# KX1_DB_DAC_2.net
KiCad netlist of a schematic drawn in Altium Designer
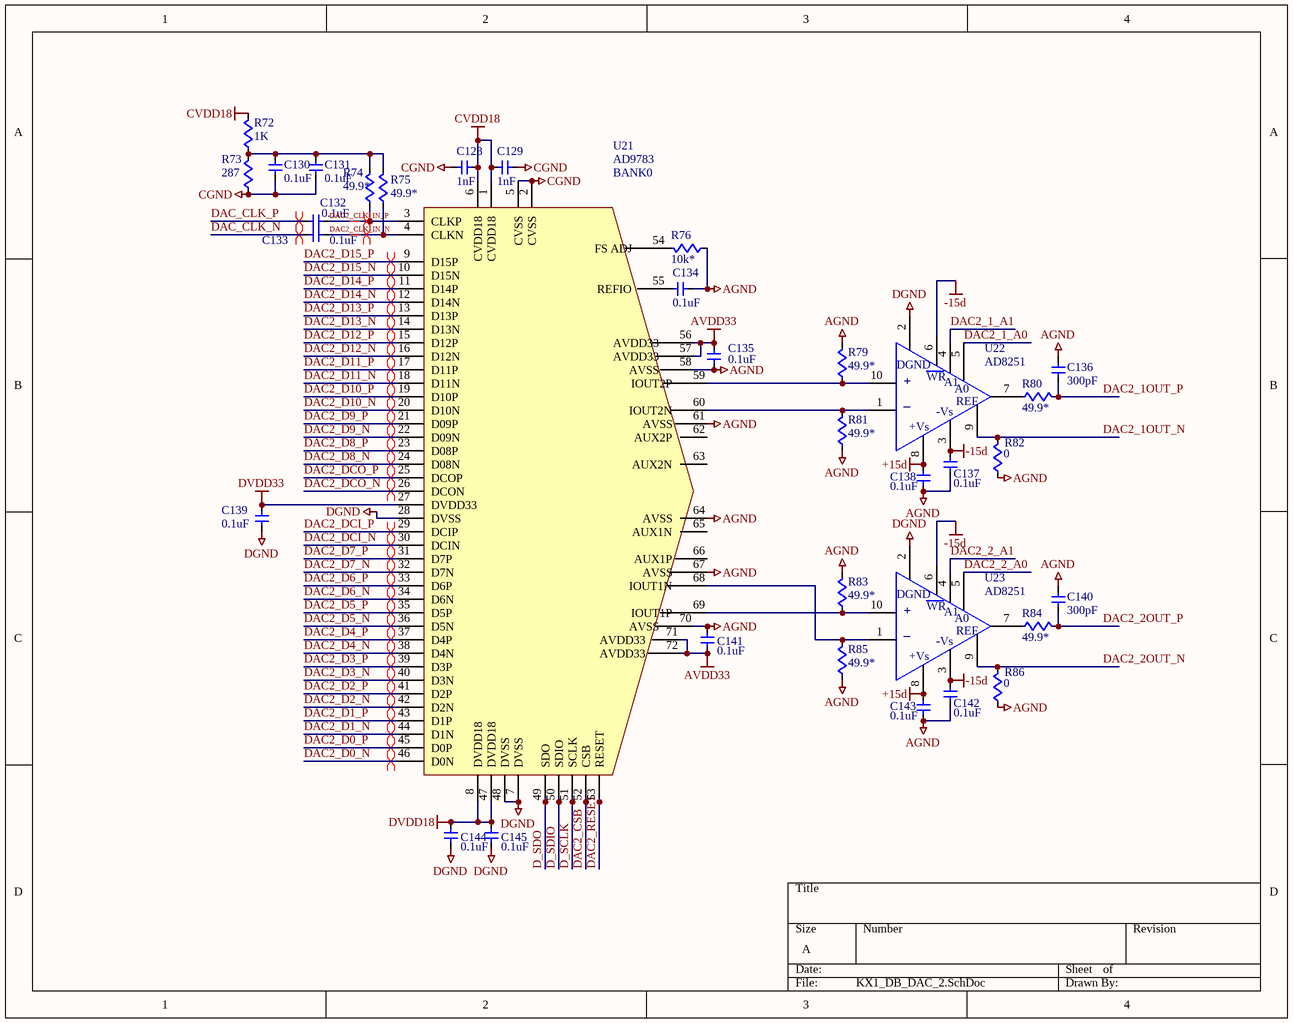
[diagram p0: KX1_DB_DAC_2.SchDoc]

(export (version "E")
  (design (tool "Eeschema 10.0.6"))
  (components
    (comp (ref "C128")
      (value "1nF")
      (footprint "0603w")
      (description "capacitor")
      (fields
        (field (name "MANUFACTURER") "Murata Electronics North America")
        (field (name "MANUFACTURER PART NUMBER") "GRM188R71H102KA01D")
      )
      (libsource (lib "KX1_DB") (part "CAP_SM_1"))
    )
    (comp (ref "C129")
      (value "1nF")
      (footprint "0603w")
      (description "capacitor")
      (fields
        (field (name "MANUFACTURER") "Murata Electronics North America")
        (field (name "MANUFACTURER PART NUMBER") "GRM188R71H102KA01D")
      )
      (libsource (lib "KX1_DB") (part "CAP_SM_1"))
    )
    (comp (ref "C130")
      (value "0.1uF")
      (footprint "0603w")
      (description "capacitor")
      (fields
        (field (name "MANUFACTURER") "Kemet")
        (field (name "MANUFACTURER PART NUMBER") "C0603C104K3RACTU")
      )
      (libsource (lib "KX1_DB") (part "CAP_SM"))
    )
    (comp (ref "C131")
      (value "0.1uF")
      (footprint "0603w")
      (description "capacitor")
      (fields
        (field (name "MANUFACTURER") "Kemet")
        (field (name "MANUFACTURER PART NUMBER") "C0603C104K3RACTU")
      )
      (libsource (lib "KX1_DB") (part "CAP_SM"))
    )
    (comp (ref "C132")
      (value "0.1uF")
      (footprint "1206")
      (description "capacitor")
      (fields
        (field (name "MANUFACTURER") "Murata Electronics North America")
        (field (name "MANUFACTURER PART NUMBER") "GRM31C5C1E104JA01L")
      )
      (libsource (lib "KX1_DB") (part "CAP_SM_1"))
    )
    (comp (ref "C133")
      (value "0.1uF")
      (footprint "1206")
      (description "capacitor")
      (fields
        (field (name "MANUFACTURER") "Murata Electronics North America")
        (field (name "MANUFACTURER PART NUMBER") "GRM31C5C1E104JA01L")
      )
      (libsource (lib "KX1_DB") (part "CAP_SM_1"))
    )
    (comp (ref "C134")
      (value "0.1uF")
      (footprint "0603w")
      (description "capacitor")
      (fields
        (field (name "MANUFACTURER") "Kemet")
        (field (name "MANUFACTURER PART NUMBER") "C0603C104K3RACTU")
      )
      (libsource (lib "KX1_DB") (part "CAP_SM_1"))
    )
    (comp (ref "C135")
      (value "0.1uF")
      (footprint "0603w")
      (description "capacitor")
      (fields
        (field (name "MANUFACTURER") "Kemet")
        (field (name "MANUFACTURER PART NUMBER") "C0603C104K3RACTU")
      )
      (libsource (lib "KX1_DB") (part "CAP_SM_1"))
    )
    (comp (ref "C136")
      (value "300pF")
      (footprint "0603w")
      (description "capacitor")
      (libsource (lib "KX1_DB") (part "CAP_SM_1"))
    )
    (comp (ref "C137")
      (value "0.1uF")
      (footprint "0603w")
      (description "capacitor")
      (fields
        (field (name "MANUFACTURER") "Kemet")
        (field (name "MANUFACTURER PART NUMBER") "C0603C104K3RACTU")
      )
      (libsource (lib "KX1_DB") (part "CAP_SM_1"))
    )
    (comp (ref "C138")
      (value "0.1uF")
      (footprint "0603w")
      (description "capacitor")
      (fields
        (field (name "MANUFACTURER") "Kemet")
        (field (name "MANUFACTURER PART NUMBER") "C0603C104K3RACTU")
      )
      (libsource (lib "KX1_DB") (part "CAP_SM_1"))
    )
    (comp (ref "C139")
      (value "0.1uF")
      (footprint "0603w")
      (description "capacitor")
      (fields
        (field (name "MANUFACTURER") "Kemet")
        (field (name "MANUFACTURER PART NUMBER") "C0603C104K3RACTU")
      )
      (libsource (lib "KX1_DB") (part "CAP_SM_1"))
    )
    (comp (ref "C140")
      (value "300pF")
      (footprint "0603w")
      (description "capacitor")
      (libsource (lib "KX1_DB") (part "CAP_SM_1"))
    )
    (comp (ref "C141")
      (value "0.1uF")
      (footprint "0603w")
      (description "capacitor")
      (fields
        (field (name "MANUFACTURER") "Kemet")
        (field (name "MANUFACTURER PART NUMBER") "C0603C104K3RACTU")
      )
      (libsource (lib "KX1_DB") (part "CAP_SM_1"))
    )
    (comp (ref "C142")
      (value "0.1uF")
      (footprint "0603w")
      (description "capacitor")
      (fields
        (field (name "MANUFACTURER") "Kemet")
        (field (name "MANUFACTURER PART NUMBER") "C0603C104K3RACTU")
      )
      (libsource (lib "KX1_DB") (part "CAP_SM_1"))
    )
    (comp (ref "C143")
      (value "0.1uF")
      (footprint "0603w")
      (description "capacitor")
      (fields
        (field (name "MANUFACTURER") "Kemet")
        (field (name "MANUFACTURER PART NUMBER") "C0603C104K3RACTU")
      )
      (libsource (lib "KX1_DB") (part "CAP_SM_1"))
    )
    (comp (ref "C144")
      (value "0.1uF")
      (footprint "0603w")
      (description "capacitor")
      (fields
        (field (name "MANUFACTURER") "Kemet")
        (field (name "MANUFACTURER PART NUMBER") "C0603C104K3RACTU")
      )
      (libsource (lib "KX1_DB") (part "CAP_SM_1"))
    )
    (comp (ref "C145")
      (value "0.1uF")
      (footprint "0603w")
      (description "capacitor")
      (fields
        (field (name "MANUFACTURER") "Kemet")
        (field (name "MANUFACTURER PART NUMBER") "C0603C104K3RACTU")
      )
      (libsource (lib "KX1_DB") (part "CAP_SM_1"))
    )
    (comp (ref "R72")
      (value "1K")
      (footprint "0603w")
      (description "resistor")
      (fields
        (field (name "MANUFACTURER") "Yageo")
        (field (name "MANUFACTURER PART NUMBER") "RC0603FR-071KL")
      )
      (libsource (lib "KX1_DB") (part "RES_SM"))
    )
    (comp (ref "R73")
      (value "287")
      (footprint "0603w")
      (description "resistor")
      (fields
        (field (name "MANUFACTURER") "Yageo")
        (field (name "MANUFACTURER PART NUMBER") "RC0603FR-07287RL")
      )
      (libsource (lib "KX1_DB") (part "RES_SM"))
    )
    (comp (ref "R74")
      (value "49.9*")
      (footprint "0603w")
      (description "resistor")
      (fields
        (field (name "MANUFACTURER") "Stackpole Electronics Inc")
        (field (name "MANUFACTURER PART NUMBER") "RNCS0603BKE49R9")
      )
      (libsource (lib "KX1_DB") (part "RES_SM"))
    )
    (comp (ref "R75")
      (value "49.9*")
      (footprint "0603w")
      (description "resistor")
      (fields
        (field (name "MANUFACTURER") "Stackpole Electronics Inc")
        (field (name "MANUFACTURER PART NUMBER") "RNCS0603BKE49R9")
      )
      (libsource (lib "KX1_DB") (part "RES_SM"))
    )
    (comp (ref "R76")
      (value "10k*")
      (footprint "0603w")
      (description "resistor")
      (fields
        (field (name "MANUFACTURER") "Susumu")
        (field (name "MANUFACTURER PART NUMBER") "RG1608P-103-B-T5")
      )
      (libsource (lib "KX1_DB") (part "RES_SM"))
    )
    (comp (ref "R79")
      (value "49.9*")
      (footprint "0603w")
      (description "resistor")
      (fields
        (field (name "MANUFACTURER") "Stackpole Electronics Inc")
        (field (name "MANUFACTURER PART NUMBER") "RNCS0603BKE49R9")
      )
      (libsource (lib "KX1_DB") (part "RES_SM"))
    )
    (comp (ref "R80")
      (value "49.9*")
      (footprint "0603w")
      (description "resistor")
      (fields
        (field (name "MANUFACTURER") "Stackpole Electronics Inc")
        (field (name "MANUFACTURER PART NUMBER") "RNCS0603BKE49R9")
      )
      (libsource (lib "KX1_DB") (part "RES_SM"))
    )
    (comp (ref "R81")
      (value "49.9*")
      (footprint "0603w")
      (description "resistor")
      (fields
        (field (name "MANUFACTURER") "Stackpole Electronics Inc")
        (field (name "MANUFACTURER PART NUMBER") "RNCS0603BKE49R9")
      )
      (libsource (lib "KX1_DB") (part "RES_SM"))
    )
    (comp (ref "R82")
      (value "0")
      (footprint "0603w")
      (description "resistor")
      (libsource (lib "KX1_DB") (part "RES_SM"))
    )
    (comp (ref "R83")
      (value "49.9*")
      (footprint "0603w")
      (description "resistor")
      (fields
        (field (name "MANUFACTURER") "Stackpole Electronics Inc")
        (field (name "MANUFACTURER PART NUMBER") "RNCS0603BKE49R9")
      )
      (libsource (lib "KX1_DB") (part "RES_SM"))
    )
    (comp (ref "R84")
      (value "49.9*")
      (footprint "0603w")
      (description "resistor")
      (fields
        (field (name "MANUFACTURER") "Stackpole Electronics Inc")
        (field (name "MANUFACTURER PART NUMBER") "RNCS0603BKE49R9")
      )
      (libsource (lib "KX1_DB") (part "RES_SM"))
    )
    (comp (ref "R85")
      (value "49.9*")
      (footprint "0603w")
      (description "resistor")
      (fields
        (field (name "MANUFACTURER") "Stackpole Electronics Inc")
        (field (name "MANUFACTURER PART NUMBER") "RNCS0603BKE49R9")
      )
      (libsource (lib "KX1_DB") (part "RES_SM"))
    )
    (comp (ref "R86")
      (value "0")
      (footprint "0603w")
      (description "resistor")
      (libsource (lib "KX1_DB") (part "RES_SM"))
    )
    (comp (ref "U21")
      (value "AD9783")
      (footprint "LFCSP72")
      (description "DAC LVDS DUAL16BIT 500MSPS")
      (libsource (lib "KX1_DB") (part "AD9783"))
    )
    (comp (ref "U22")
      (value "AD8251")
      (footprint "MSOP10sm")
      (description "IC AMP INST ICMOS LDRIFT 10MSOP")
      (libsource (lib "KX1_DB") (part "AD8251"))
    )
    (comp (ref "U23")
      (value "AD8251")
      (footprint "MSOP10sm")
      (description "IC AMP INST ICMOS LDRIFT 10MSOP")
      (libsource (lib "KX1_DB") (part "AD8251"))
    )
  )
  (nets
    (net (code "1") (name "+15d") (class "Default")
      (node (ref "C138") (pin "2") (pintype "passive"))
      (node (ref "C143") (pin "2") (pintype "passive"))
      (node (ref "U22") (pin "8") (pintype "passive"))
      (node (ref "U23") (pin "8") (pintype "passive"))
    )
    (net (code "2") (name "-15d") (class "Default")
      (node (ref "C137") (pin "2") (pintype "passive"))
      (node (ref "C142") (pin "2") (pintype "passive"))
      (node (ref "U22") (pin "3") (pintype "passive"))
      (node (ref "U22") (pin "6") (pintype "passive"))
      (node (ref "U23") (pin "3") (pintype "passive"))
      (node (ref "U23") (pin "6") (pintype "passive"))
    )
    (net (code "3") (name "/DAC2_1OUT_N") (class "Default")
      (node (ref "R82") (pin "2") (pintype "passive"))
      (node (ref "U22") (pin "9") (pintype "passive"))
    )
    (net (code "4") (name "/DAC2_1OUT_P") (class "Default")
      (node (ref "C136") (pin "1") (pintype "passive"))
      (node (ref "R80") (pin "2") (pintype "passive"))
    )
    (net (code "5") (name "/DAC2_1_A0") (class "Default") (node (ref "U22") (pin "5") (pintype "passive")))
    (net (code "6") (name "/DAC2_1_A1") (class "Default") (node (ref "U22") (pin "4") (pintype "passive")))
    (net (code "7") (name "/DAC2_2OUT_N") (class "Default")
      (node (ref "R86") (pin "2") (pintype "passive"))
      (node (ref "U23") (pin "9") (pintype "passive"))
    )
    (net (code "8") (name "/DAC2_2OUT_P") (class "Default")
      (node (ref "C140") (pin "1") (pintype "passive"))
      (node (ref "R84") (pin "2") (pintype "passive"))
    )
    (net (code "9") (name "/DAC2_2_A0") (class "Default") (node (ref "U23") (pin "5") (pintype "passive")))
    (net (code "10") (name "/DAC2_2_A1") (class "Default") (node (ref "U23") (pin "4") (pintype "passive")))
    (net (code "11") (name "/DAC2_CLK_IN_N") (class "Default")
      (node (ref "C133") (pin "2") (pintype "passive"))
      (node (ref "R75") (pin "1") (pintype "passive"))
      (node (ref "U21") (pin "4") (pinfunction "CLKN_4") (pintype "passive"))
    )
    (net (code "12") (name "/DAC2_CLK_IN_P") (class "Default")
      (node (ref "C132") (pin "2") (pintype "passive"))
      (node (ref "R74") (pin "1") (pintype "passive"))
      (node (ref "U21") (pin "3") (pinfunction "CLKP_3") (pintype "passive"))
    )
    (net (code "13") (name "/DAC2_CSB") (class "Default")
      (node (ref "U21") (pin "52") (pinfunction "CSB_52") (pintype "passive"))
    )
    (net (code "14") (name "/DAC2_D0_N") (class "Default")
      (node (ref "U21") (pin "46") (pinfunction "D0N_46") (pintype "passive"))
    )
    (net (code "15") (name "/DAC2_D0_P") (class "Default")
      (node (ref "U21") (pin "45") (pinfunction "D0P_45") (pintype "passive"))
    )
    (net (code "16") (name "/DAC2_D1_N") (class "Default")
      (node (ref "U21") (pin "44") (pinfunction "D1N_44") (pintype "passive"))
    )
    (net (code "17") (name "/DAC2_D1_P") (class "Default")
      (node (ref "U21") (pin "43") (pinfunction "D1P_43") (pintype "passive"))
    )
    (net (code "18") (name "/DAC2_D2_N") (class "Default")
      (node (ref "U21") (pin "42") (pinfunction "D2N_42") (pintype "passive"))
    )
    (net (code "19") (name "/DAC2_D2_P") (class "Default")
      (node (ref "U21") (pin "41") (pinfunction "D2P_41") (pintype "passive"))
    )
    (net (code "20") (name "/DAC2_D3_N") (class "Default")
      (node (ref "U21") (pin "40") (pinfunction "D3N_40") (pintype "passive"))
    )
    (net (code "21") (name "/DAC2_D3_P") (class "Default")
      (node (ref "U21") (pin "39") (pinfunction "D3P_39") (pintype "passive"))
    )
    (net (code "22") (name "/DAC2_D4_N") (class "Default")
      (node (ref "U21") (pin "38") (pinfunction "D4N_38") (pintype "passive"))
    )
    (net (code "23") (name "/DAC2_D4_P") (class "Default")
      (node (ref "U21") (pin "37") (pinfunction "D4P_37") (pintype "passive"))
    )
    (net (code "24") (name "/DAC2_D5_N") (class "Default")
      (node (ref "U21") (pin "36") (pinfunction "D5N_36") (pintype "passive"))
    )
    (net (code "25") (name "/DAC2_D5_P") (class "Default")
      (node (ref "U21") (pin "35") (pinfunction "D5P_35") (pintype "passive"))
    )
    (net (code "26") (name "/DAC2_D6_N") (class "Default")
      (node (ref "U21") (pin "34") (pinfunction "D6N_34") (pintype "passive"))
    )
    (net (code "27") (name "/DAC2_D6_P") (class "Default")
      (node (ref "U21") (pin "33") (pinfunction "D6P_33") (pintype "passive"))
    )
    (net (code "28") (name "/DAC2_D7_N") (class "Default")
      (node (ref "U21") (pin "32") (pinfunction "D7N_32") (pintype "passive"))
    )
    (net (code "29") (name "/DAC2_D7_P") (class "Default")
      (node (ref "U21") (pin "31") (pinfunction "D7P_31") (pintype "passive"))
    )
    (net (code "30") (name "/DAC2_D8_N") (class "Default")
      (node (ref "U21") (pin "24") (pinfunction "D08N_24") (pintype "passive"))
    )
    (net (code "31") (name "/DAC2_D8_P") (class "Default")
      (node (ref "U21") (pin "23") (pinfunction "D08P_23") (pintype "passive"))
    )
    (net (code "32") (name "/DAC2_D9_N") (class "Default")
      (node (ref "U21") (pin "22") (pinfunction "D09N_22") (pintype "passive"))
    )
    (net (code "33") (name "/DAC2_D9_P") (class "Default")
      (node (ref "U21") (pin "21") (pinfunction "D09P_21") (pintype "passive"))
    )
    (net (code "34") (name "/DAC2_D10_N") (class "Default")
      (node (ref "U21") (pin "20") (pinfunction "D10N_20") (pintype "passive"))
    )
    (net (code "35") (name "/DAC2_D10_P") (class "Default")
      (node (ref "U21") (pin "19") (pinfunction "D10P_19") (pintype "passive"))
    )
    (net (code "36") (name "/DAC2_D11_N") (class "Default")
      (node (ref "U21") (pin "18") (pinfunction "D11N_18") (pintype "passive"))
    )
    (net (code "37") (name "/DAC2_D11_P") (class "Default")
      (node (ref "U21") (pin "17") (pinfunction "D11P_17") (pintype "passive"))
    )
    (net (code "38") (name "/DAC2_D12_N") (class "Default")
      (node (ref "U21") (pin "16") (pinfunction "D12N_16") (pintype "passive"))
    )
    (net (code "39") (name "/DAC2_D12_P") (class "Default")
      (node (ref "U21") (pin "15") (pinfunction "D12P_15") (pintype "passive"))
    )
    (net (code "40") (name "/DAC2_D13_N") (class "Default")
      (node (ref "U21") (pin "14") (pinfunction "D13N_14") (pintype "passive"))
    )
    (net (code "41") (name "/DAC2_D13_P") (class "Default")
      (node (ref "U21") (pin "13") (pinfunction "D13P_13") (pintype "passive"))
    )
    (net (code "42") (name "/DAC2_D14_N") (class "Default")
      (node (ref "U21") (pin "12") (pinfunction "D14N_12") (pintype "passive"))
    )
    (net (code "43") (name "/DAC2_D14_P") (class "Default")
      (node (ref "U21") (pin "11") (pinfunction "D14P_11") (pintype "passive"))
    )
    (net (code "44") (name "/DAC2_D15_N") (class "Default")
      (node (ref "U21") (pin "10") (pinfunction "D15N_10") (pintype "passive"))
    )
    (net (code "45") (name "/DAC2_D15_P") (class "Default")
      (node (ref "U21") (pin "9") (pinfunction "D15P_9") (pintype "passive"))
    )
    (net (code "46") (name "/DAC2_DCI_N") (class "Default")
      (node (ref "U21") (pin "30") (pinfunction "DCIN_30") (pintype "passive"))
    )
    (net (code "47") (name "/DAC2_DCI_P") (class "Default")
      (node (ref "U21") (pin "29") (pinfunction "DCIP_29") (pintype "passive"))
    )
    (net (code "48") (name "/DAC2_DCO_N") (class "Default")
      (node (ref "U21") (pin "26") (pinfunction "DCON_26") (pintype "passive"))
    )
    (net (code "49") (name "/DAC2_DCO_P") (class "Default")
      (node (ref "U21") (pin "25") (pinfunction "DCOP_25") (pintype "passive"))
    )
    (net (code "50") (name "/DAC2_RESET") (class "Default")
      (node (ref "U21") (pin "53") (pinfunction "RESET_53") (pintype "passive"))
    )
    (net (code "51") (name "/DAC_CLK_N") (class "Default") (node (ref "C133") (pin "1") (pintype "passive")))
    (net (code "52") (name "/DAC_CLK_P") (class "Default") (node (ref "C132") (pin "1") (pintype "passive")))
    (net (code "53") (name "/D_SCLK") (class "Default")
      (node (ref "U21") (pin "51") (pinfunction "SCLK_51") (pintype "passive"))
    )
    (net (code "54") (name "/D_SDIO") (class "Default")
      (node (ref "U21") (pin "50") (pinfunction "SDIO_50") (pintype "passive"))
    )
    (net (code "55") (name "/D_SDO") (class "Default")
      (node (ref "U21") (pin "49") (pinfunction "SDO_49") (pintype "passive"))
    )
    (net (code "56") (name "AGND") (class "Default")
      (node (ref "C134") (pin "2") (pintype "passive"))
      (node (ref "C135") (pin "1") (pintype "passive"))
      (node (ref "C136") (pin "2") (pintype "passive"))
      (node (ref "C137") (pin "1") (pintype "passive"))
      (node (ref "C138") (pin "1") (pintype "passive"))
      (node (ref "C140") (pin "2") (pintype "passive"))
      (node (ref "C141") (pin "2") (pintype "passive"))
      (node (ref "C142") (pin "1") (pintype "passive"))
      (node (ref "C143") (pin "1") (pintype "passive"))
      (node (ref "R76") (pin "1") (pintype "passive"))
      (node (ref "R79") (pin "2") (pintype "passive"))
      (node (ref "R81") (pin "1") (pintype "passive"))
      (node (ref "R82") (pin "1") (pintype "passive"))
      (node (ref "R83") (pin "2") (pintype "passive"))
      (node (ref "R85") (pin "1") (pintype "passive"))
      (node (ref "R86") (pin "1") (pintype "passive"))
      (node (ref "U21") (pin "58") (pinfunction "AVSS_58") (pintype "passive"))
      (node (ref "U21") (pin "61") (pinfunction "AVSS_61") (pintype "passive"))
      (node (ref "U21") (pin "64") (pinfunction "AVSS_64") (pintype "passive"))
      (node (ref "U21") (pin "67") (pinfunction "AVSS_67") (pintype "passive"))
      (node (ref "U21") (pin "70") (pinfunction "AVSS_70") (pintype "passive"))
    )
    (net (code "57") (name "AVDD33") (class "Default")
      (node (ref "C135") (pin "2") (pintype "passive"))
      (node (ref "C141") (pin "1") (pintype "passive"))
      (node (ref "U21") (pin "56") (pinfunction "AVDD33_56") (pintype "passive"))
      (node (ref "U21") (pin "57") (pinfunction "AVDD33_57") (pintype "passive"))
      (node (ref "U21") (pin "71") (pinfunction "AVDD33_71") (pintype "passive"))
      (node (ref "U21") (pin "72") (pinfunction "AVDD33_72") (pintype "passive"))
    )
    (net (code "58") (name "CGND") (class "Default")
      (node (ref "C128") (pin "2") (pintype "passive"))
      (node (ref "C129") (pin "2") (pintype "passive"))
      (node (ref "C130") (pin "2") (pintype "passive"))
      (node (ref "C131") (pin "2") (pintype "passive"))
      (node (ref "R73") (pin "1") (pintype "passive"))
      (node (ref "U21") (pin "2") (pinfunction "CVSS_2") (pintype "passive"))
      (node (ref "U21") (pin "5") (pinfunction "CVSS_5") (pintype "passive"))
    )
    (net (code "59") (name "CVDD18") (class "Default")
      (node (ref "C128") (pin "1") (pintype "passive"))
      (node (ref "C129") (pin "1") (pintype "passive"))
      (node (ref "R72") (pin "2") (pintype "passive"))
      (node (ref "U21") (pin "1") (pinfunction "CVDD18_1") (pintype "passive"))
      (node (ref "U21") (pin "6") (pinfunction "CVDD18_6") (pintype "passive"))
    )
    (net (code "60") (name "DGND") (class "Default")
      (node (ref "C139") (pin "2") (pintype "passive"))
      (node (ref "C144") (pin "1") (pintype "passive"))
      (node (ref "C145") (pin "1") (pintype "passive"))
      (node (ref "U21") (pin "28") (pinfunction "DVSS_28") (pintype "passive"))
      (node (ref "U21") (pin "48") (pinfunction "DVSS_48") (pintype "passive"))
      (node (ref "U21") (pin "7") (pinfunction "DVSS_7") (pintype "passive"))
      (node (ref "U22") (pin "2") (pintype "passive"))
      (node (ref "U23") (pin "2") (pintype "passive"))
    )
    (net (code "61") (name "DVDD18") (class "Default")
      (node (ref "C144") (pin "2") (pintype "passive"))
      (node (ref "C145") (pin "2") (pintype "passive"))
      (node (ref "U21") (pin "47") (pinfunction "DVDD18_47") (pintype "passive"))
      (node (ref "U21") (pin "8") (pinfunction "DVDD18_8") (pintype "passive"))
    )
    (net (code "62") (name "DVDD33") (class "Default")
      (node (ref "C139") (pin "1") (pintype "passive"))
      (node (ref "U21") (pin "27") (pinfunction "DVDD33_27") (pintype "passive"))
    )
    (net (code "63") (name "Net-(C130-Pad1)") (class "Default")
      (node (ref "C130") (pin "1") (pintype "passive"))
      (node (ref "C131") (pin "1") (pintype "passive"))
      (node (ref "R72") (pin "1") (pintype "passive"))
      (node (ref "R73") (pin "2") (pintype "passive"))
      (node (ref "R74") (pin "2") (pintype "passive"))
      (node (ref "R75") (pin "2") (pintype "passive"))
    )
    (net (code "64") (name "Net-(R80-Pad1)") (class "Default")
      (node (ref "R80") (pin "1") (pintype "passive"))
      (node (ref "U22") (pin "7") (pintype "passive"))
    )
    (net (code "65") (name "Net-(R84-Pad1)") (class "Default")
      (node (ref "R84") (pin "1") (pintype "passive"))
      (node (ref "U23") (pin "7") (pintype "passive"))
    )
    (net (code "66") (name "Net-(U21-FS_ADJ)") (class "Default")
      (node (ref "R76") (pin "2") (pintype "passive"))
      (node (ref "U21") (pin "54") (pinfunction "FS_ADJ_54") (pintype "passive"))
    )
    (net (code "67") (name "Net-(U21-IOUT1N)") (class "Default")
      (node (ref "R85") (pin "2") (pintype "passive"))
      (node (ref "U21") (pin "68") (pinfunction "IOUT1N_68") (pintype "passive"))
      (node (ref "U23") (pin "1") (pintype "passive"))
    )
    (net (code "68") (name "Net-(U21-IOUT1P)") (class "Default")
      (node (ref "R83") (pin "1") (pintype "passive"))
      (node (ref "U21") (pin "69") (pinfunction "IOUT1P_69") (pintype "passive"))
      (node (ref "U23") (pin "10") (pintype "passive"))
    )
    (net (code "69") (name "Net-(U21-IOUT2N)") (class "Default")
      (node (ref "R81") (pin "2") (pintype "passive"))
      (node (ref "U21") (pin "60") (pinfunction "IOUT2N_60") (pintype "passive"))
      (node (ref "U22") (pin "1") (pintype "passive"))
    )
    (net (code "70") (name "Net-(U21-IOUT2P)") (class "Default")
      (node (ref "R79") (pin "1") (pintype "passive"))
      (node (ref "U21") (pin "59") (pinfunction "IOUT2P_59") (pintype "passive"))
      (node (ref "U22") (pin "10") (pintype "passive"))
    )
    (net (code "71") (name "Net-(U21-REFIO)") (class "Default")
      (node (ref "C134") (pin "1") (pintype "passive"))
      (node (ref "U21") (pin "55") (pinfunction "REFIO_55") (pintype "passive"))
    )
    (net (code "72") (name "unconnected-(U21-AUX1N-Pad65)") (class "Default")
      (node (ref "U21") (pin "65") (pinfunction "AUX1N_65") (pintype "passive"))
    )
    (net (code "73") (name "unconnected-(U21-AUX1P-Pad66)") (class "Default")
      (node (ref "U21") (pin "66") (pinfunction "AUX1P_66") (pintype "passive"))
    )
    (net (code "74") (name "unconnected-(U21-AUX2N-Pad63)") (class "Default")
      (node (ref "U21") (pin "63") (pinfunction "AUX2N_63") (pintype "passive"))
    )
    (net (code "75") (name "unconnected-(U21-AUX2P-Pad62)") (class "Default")
      (node (ref "U21") (pin "62") (pinfunction "AUX2P_62") (pintype "passive"))
    )
  )
)
